# Raspberry-Pi-Header.net
KiCad netlist of a schematic drawn in EAGLE
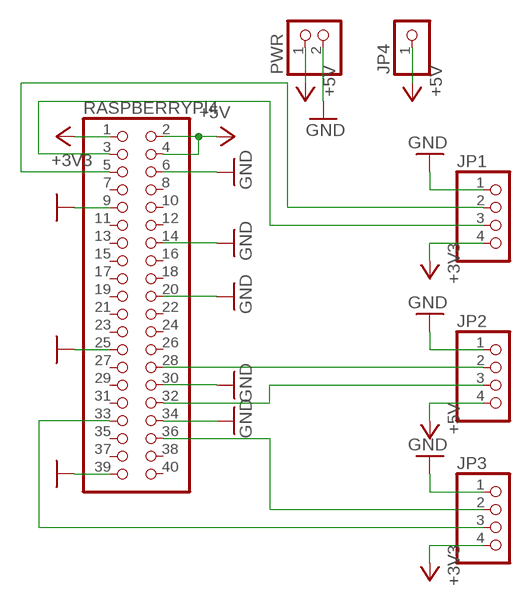
[diagram p0: schematic, sheet 1]

(export (version "E")
  (design (tool "Eeschema 10.0.6"))
  (components
    (comp (ref "JP1")
      (value "PINHD-1X4/90")
      (footprint "eagle-import:1X04_90")
      (libsource (lib "eagle-import") (part "PINHD-1X4/90"))
    )
    (comp (ref "JP2")
      (value "PINHD-1X4/90")
      (footprint "eagle-import:1X04_90")
      (libsource (lib "eagle-import") (part "PINHD-1X4/90"))
    )
    (comp (ref "JP3")
      (value "PINHD-1X4/90")
      (footprint "eagle-import:1X04_90")
      (libsource (lib "eagle-import") (part "PINHD-1X4/90"))
    )
    (comp (ref "JP4")
      (value "PINHD-1X1")
      (footprint "eagle-import:1X01")
      (libsource (lib "eagle-import") (part "PINHD-1X1"))
    )
    (comp (ref "PWR")
      (value "PINHD-1X2/90")
      (footprint "eagle-import:1X02_90")
      (libsource (lib "eagle-import") (part "PINHD-1X2/90"))
    )
    (comp (ref "RASPBERRYPI4")
      (value "PINHD-2X20")
      (footprint "eagle-import:2X20")
      (libsource (lib "eagle-import") (part "PINHD-2X20"))
    )
  )
  (nets
    (net (code "1") (name "+3V3") (class "Default")
      (node (ref "JP1") (pin "4") (pinfunction "4_4") (pintype "passive"))
      (node (ref "JP3") (pin "4") (pinfunction "4_4") (pintype "passive"))
      (node (ref "RASPBERRYPI4") (pin "1") (pinfunction "1_1") (pintype "passive"))
    )
    (net (code "2") (name "+5V") (class "Default")
      (node (ref "JP2") (pin "4") (pinfunction "4_4") (pintype "passive"))
      (node (ref "JP4") (pin "1") (pinfunction "1_1") (pintype "passive"))
      (node (ref "PWR") (pin "1") (pinfunction "1_1") (pintype "passive"))
      (node (ref "RASPBERRYPI4") (pin "2") (pinfunction "2_2") (pintype "passive"))
      (node (ref "RASPBERRYPI4") (pin "4") (pinfunction "4_4") (pintype "passive"))
    )
    (net (code "3") (name "GND") (class "Default")
      (node (ref "JP1") (pin "1") (pinfunction "1_1") (pintype "passive"))
      (node (ref "JP2") (pin "1") (pinfunction "1_1") (pintype "passive"))
      (node (ref "JP3") (pin "1") (pinfunction "1_1") (pintype "passive"))
      (node (ref "PWR") (pin "2") (pinfunction "2_2") (pintype "passive"))
      (node (ref "RASPBERRYPI4") (pin "14") (pinfunction "14_14") (pintype "passive"))
      (node (ref "RASPBERRYPI4") (pin "20") (pinfunction "20_20") (pintype "passive"))
      (node (ref "RASPBERRYPI4") (pin "25") (pinfunction "25_25") (pintype "passive"))
      (node (ref "RASPBERRYPI4") (pin "30") (pinfunction "30_30") (pintype "passive"))
      (node (ref "RASPBERRYPI4") (pin "34") (pinfunction "34_34") (pintype "passive"))
      (node (ref "RASPBERRYPI4") (pin "39") (pinfunction "39_39") (pintype "passive"))
      (node (ref "RASPBERRYPI4") (pin "6") (pinfunction "6_6") (pintype "passive"))
      (node (ref "RASPBERRYPI4") (pin "9") (pinfunction "9_9") (pintype "passive"))
    )
    (net (code "4") (name "Net-(JP1-Pad2)") (class "Default")
      (node (ref "JP1") (pin "2") (pinfunction "2_2") (pintype "passive"))
      (node (ref "RASPBERRYPI4") (pin "5") (pinfunction "5_5") (pintype "passive"))
    )
    (net (code "5") (name "Net-(JP1-Pad3)") (class "Default")
      (node (ref "JP1") (pin "3") (pinfunction "3_3") (pintype "passive"))
      (node (ref "RASPBERRYPI4") (pin "3") (pinfunction "3_3") (pintype "passive"))
    )
    (net (code "6") (name "Net-(JP2-Pad2)") (class "Default")
      (node (ref "JP2") (pin "2") (pinfunction "2_2") (pintype "passive"))
      (node (ref "RASPBERRYPI4") (pin "28") (pinfunction "28_28") (pintype "passive"))
    )
    (net (code "7") (name "Net-(JP2-Pad3)") (class "Default")
      (node (ref "JP2") (pin "3") (pinfunction "3_3") (pintype "passive"))
      (node (ref "RASPBERRYPI4") (pin "32") (pinfunction "32_32") (pintype "passive"))
    )
    (net (code "8") (name "Net-(JP3-Pad2)") (class "Default")
      (node (ref "JP3") (pin "2") (pinfunction "2_2") (pintype "passive"))
      (node (ref "RASPBERRYPI4") (pin "36") (pinfunction "36_36") (pintype "passive"))
    )
    (net (code "9") (name "Net-(JP3-Pad3)") (class "Default")
      (node (ref "JP3") (pin "3") (pinfunction "3_3") (pintype "passive"))
      (node (ref "RASPBERRYPI4") (pin "33") (pinfunction "33_33") (pintype "passive"))
    )
    (net (code "10") (name "unconnected-(RASPBERRYPI4-Pad7)") (class "Default")
      (node (ref "RASPBERRYPI4") (pin "7") (pinfunction "7_7") (pintype "passive"))
    )
    (net (code "11") (name "unconnected-(RASPBERRYPI4-Pad8)") (class "Default")
      (node (ref "RASPBERRYPI4") (pin "8") (pinfunction "8_8") (pintype "passive"))
    )
    (net (code "12") (name "unconnected-(RASPBERRYPI4-Pad10)") (class "Default")
      (node (ref "RASPBERRYPI4") (pin "10") (pinfunction "10_10") (pintype "passive"))
    )
    (net (code "13") (name "unconnected-(RASPBERRYPI4-Pad11)") (class "Default")
      (node (ref "RASPBERRYPI4") (pin "11") (pinfunction "11_11") (pintype "passive"))
    )
    (net (code "14") (name "unconnected-(RASPBERRYPI4-Pad12)") (class "Default")
      (node (ref "RASPBERRYPI4") (pin "12") (pinfunction "12_12") (pintype "passive"))
    )
    (net (code "15") (name "unconnected-(RASPBERRYPI4-Pad13)") (class "Default")
      (node (ref "RASPBERRYPI4") (pin "13") (pinfunction "13_13") (pintype "passive"))
    )
    (net (code "16") (name "unconnected-(RASPBERRYPI4-Pad15)") (class "Default")
      (node (ref "RASPBERRYPI4") (pin "15") (pinfunction "15_15") (pintype "passive"))
    )
    (net (code "17") (name "unconnected-(RASPBERRYPI4-Pad16)") (class "Default")
      (node (ref "RASPBERRYPI4") (pin "16") (pinfunction "16_16") (pintype "passive"))
    )
    (net (code "18") (name "unconnected-(RASPBERRYPI4-Pad17)") (class "Default")
      (node (ref "RASPBERRYPI4") (pin "17") (pinfunction "17_17") (pintype "passive"))
    )
    (net (code "19") (name "unconnected-(RASPBERRYPI4-Pad18)") (class "Default")
      (node (ref "RASPBERRYPI4") (pin "18") (pinfunction "18_18") (pintype "passive"))
    )
    (net (code "20") (name "unconnected-(RASPBERRYPI4-Pad19)") (class "Default")
      (node (ref "RASPBERRYPI4") (pin "19") (pinfunction "19_19") (pintype "passive"))
    )
    (net (code "21") (name "unconnected-(RASPBERRYPI4-Pad21)") (class "Default")
      (node (ref "RASPBERRYPI4") (pin "21") (pinfunction "21_21") (pintype "passive"))
    )
    (net (code "22") (name "unconnected-(RASPBERRYPI4-Pad22)") (class "Default")
      (node (ref "RASPBERRYPI4") (pin "22") (pinfunction "22_22") (pintype "passive"))
    )
    (net (code "23") (name "unconnected-(RASPBERRYPI4-Pad23)") (class "Default")
      (node (ref "RASPBERRYPI4") (pin "23") (pinfunction "23_23") (pintype "passive"))
    )
    (net (code "24") (name "unconnected-(RASPBERRYPI4-Pad24)") (class "Default")
      (node (ref "RASPBERRYPI4") (pin "24") (pinfunction "24_24") (pintype "passive"))
    )
    (net (code "25") (name "unconnected-(RASPBERRYPI4-Pad26)") (class "Default")
      (node (ref "RASPBERRYPI4") (pin "26") (pinfunction "26_26") (pintype "passive"))
    )
    (net (code "26") (name "unconnected-(RASPBERRYPI4-Pad27)") (class "Default")
      (node (ref "RASPBERRYPI4") (pin "27") (pinfunction "27_27") (pintype "passive"))
    )
    (net (code "27") (name "unconnected-(RASPBERRYPI4-Pad29)") (class "Default")
      (node (ref "RASPBERRYPI4") (pin "29") (pinfunction "29_29") (pintype "passive"))
    )
    (net (code "28") (name "unconnected-(RASPBERRYPI4-Pad31)") (class "Default")
      (node (ref "RASPBERRYPI4") (pin "31") (pinfunction "31_31") (pintype "passive"))
    )
    (net (code "29") (name "unconnected-(RASPBERRYPI4-Pad35)") (class "Default")
      (node (ref "RASPBERRYPI4") (pin "35") (pinfunction "35_35") (pintype "passive"))
    )
    (net (code "30") (name "unconnected-(RASPBERRYPI4-Pad37)") (class "Default")
      (node (ref "RASPBERRYPI4") (pin "37") (pinfunction "37_37") (pintype "passive"))
    )
    (net (code "31") (name "unconnected-(RASPBERRYPI4-Pad38)") (class "Default")
      (node (ref "RASPBERRYPI4") (pin "38") (pinfunction "38_38") (pintype "passive"))
    )
    (net (code "32") (name "unconnected-(RASPBERRYPI4-Pad40)") (class "Default")
      (node (ref "RASPBERRYPI4") (pin "40") (pinfunction "40_40") (pintype "passive"))
    )
  )
)
